# SD_-_Sensor_2021-02-24.net
KiCad netlist of a schematic drawn in EasyEDA
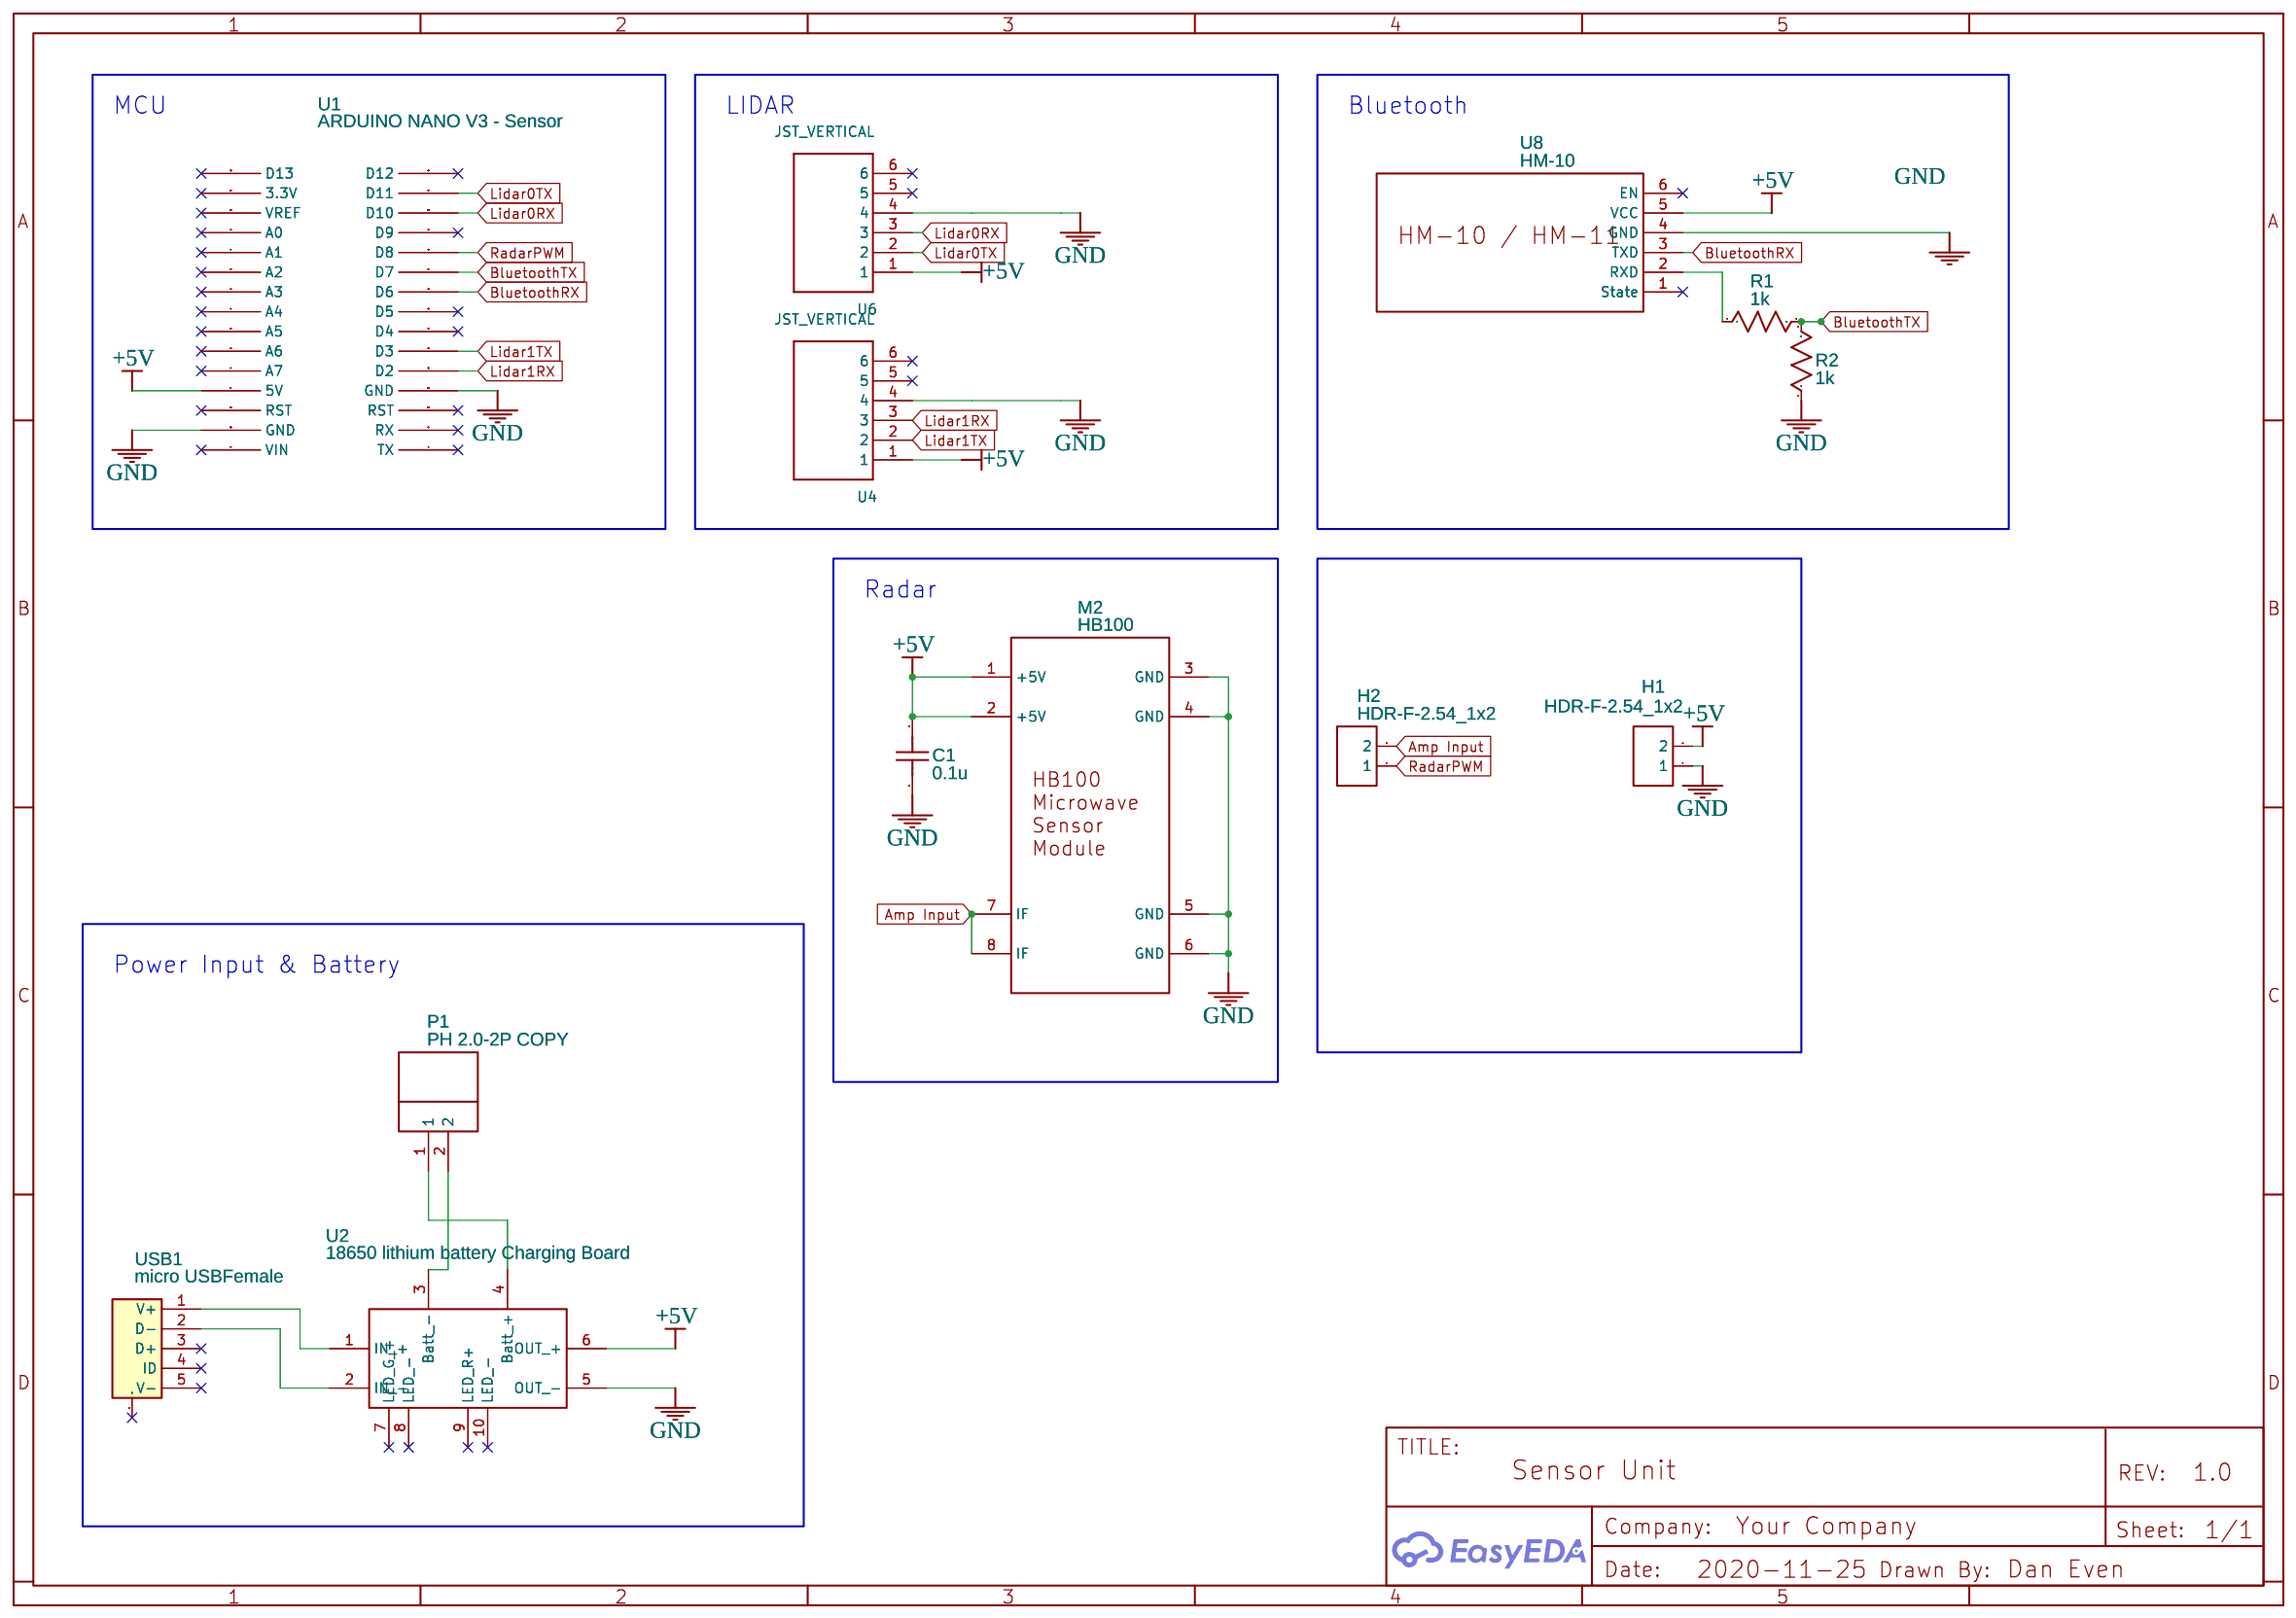
[diagram p0: schematic sheet]

(export (version "E")
  (design (tool "Eeschema 10.0.6"))
  (components
    (comp (ref "C1") (value "0.1u") (libsource (lib "") (part "C_RAD-0.1_US")))
    (comp (ref "H1")
      (value "HDR-F-2.54_1x2")
      (fields (field (name "BOM_Supplier Part") "C49661"))
      (libsource (lib "") (part "HDR-F-2.54_1x2"))
    )
    (comp (ref "H2")
      (value "HDR-F-2.54_1x2")
      (fields (field (name "BOM_Supplier Part") "C49661"))
      (libsource (lib "") (part "HDR-F-2.54_1x2"))
    )
    (comp (ref "M2") (value "HB100") (libsource (lib "") (part "HB100")))
    (comp (ref "P1")
      (value "PH 2.0-2P COPY")
      (fields (field (name "BOM_Manufacturer Part") "PH 2.0-2P"))
      (libsource (lib "") (part "PH 2.0-2P COPY"))
    )
    (comp (ref "R1") (value "1k") (libsource (lib "") (part "R_AXIAL-0.4_US_1")))
    (comp (ref "R2") (value "1k") (libsource (lib "") (part "R_AXIAL-0.4_US")))
    (comp (ref "U1")
      (value "ARDUINO NANO V3 - Sensor")
      (fields (field (name "BOM_Manufacturer Part") "arduino_nano1"))
      (libsource (lib "") (part "ARDUINO NANO V3"))
    )
    (comp (ref "U2")
      (value "18650 lithium battery Charging Board")
      (libsource (lib "") (part "18650 lithium battery Charging Board"))
    )
    (comp (ref "U4") (value "JST_VERTICAL") (libsource (lib "") (part "Unknown_405_-600")))
    (comp (ref "U6") (value "JST_VERTICAL") (libsource (lib "") (part "Unknown_405_-695")))
    (comp (ref "U8") (value "HM-10") (libsource (lib "") (part "HM-10")))
    (comp (ref "USB1")
      (value "micro USBFemale")
      (fields (field (name "BOM_Supplier Part") "C10418"))
      (libsource (lib "") (part "micro USBFemale"))
    )
  )
  (nets
    (net (code "1") (name "+5V") (class "Default")
      (node (ref "C1") (pin "2") (pinfunction "2_2") (pintype "unspecified"))
      (node (ref "H1") (pin "2") (pinfunction "2_2") (pintype "input"))
      (node (ref "M2") (pin "1") (pinfunction "+5V_1") (pintype "unspecified"))
      (node (ref "M2") (pin "2") (pinfunction "+5V_2") (pintype "unspecified"))
      (node (ref "U1") (pin "5V") (pinfunction "5V_5V") (pintype "unspecified"))
      (node (ref "U2") (pin "6") (pinfunction "OUT_+_6") (pintype "unspecified"))
      (node (ref "U4") (pin "1") (pinfunction "1_1") (pintype "bidirectional"))
      (node (ref "U6") (pin "1") (pinfunction "1_1") (pintype "bidirectional"))
      (node (ref "U8") (pin "5") (pinfunction "VCC_5") (pintype "unspecified"))
    )
    (net (code "2") (name "Amp Input") (class "Default")
      (node (ref "H2") (pin "2") (pinfunction "2_2") (pintype "input"))
      (node (ref "M2") (pin "7") (pinfunction "IF_7") (pintype "unspecified"))
      (node (ref "M2") (pin "8") (pinfunction "IF_8") (pintype "unspecified"))
    )
    (net (code "3") (name "BluetoothRX") (class "Default")
      (node (ref "U1") (pin "D6") (pinfunction "D6_D6") (pintype "unspecified"))
      (node (ref "U8") (pin "3") (pinfunction "TXD_3") (pintype "unspecified"))
    )
    (net (code "4") (name "BluetoothTX") (class "Default")
      (node (ref "R1") (pin "2") (pinfunction "2_2") (pintype "unspecified"))
      (node (ref "R2") (pin "2") (pinfunction "2_2") (pintype "unspecified"))
      (node (ref "U1") (pin "D7") (pinfunction "D7_D7") (pintype "unspecified"))
    )
    (net (code "5") (name "GND") (class "Default")
      (node (ref "C1") (pin "1") (pinfunction "1_1") (pintype "unspecified"))
      (node (ref "H1") (pin "1") (pinfunction "1_1") (pintype "input"))
      (node (ref "M2") (pin "3") (pinfunction "GND_3") (pintype "unspecified"))
      (node (ref "M2") (pin "4") (pinfunction "GND_4") (pintype "unspecified"))
      (node (ref "M2") (pin "5") (pinfunction "GND_5") (pintype "unspecified"))
      (node (ref "M2") (pin "6") (pinfunction "GND_6") (pintype "unspecified"))
      (node (ref "R2") (pin "1") (pinfunction "1_1") (pintype "unspecified"))
      (node (ref "U1") (pin "GND1") (pinfunction "GND_GND1") (pintype "unspecified"))
      (node (ref "U1") (pin "GND2") (pinfunction "GND_GND2") (pintype "unspecified"))
      (node (ref "U2") (pin "5") (pinfunction "OUT_-_5") (pintype "unspecified"))
      (node (ref "U4") (pin "4") (pinfunction "4_4") (pintype "bidirectional"))
      (node (ref "U6") (pin "4") (pinfunction "4_4") (pintype "bidirectional"))
      (node (ref "U8") (pin "4") (pinfunction "GND_4") (pintype "unspecified"))
    )
    (net (code "6") (name "Lidar0RX") (class "Default")
      (node (ref "U1") (pin "D10") (pinfunction "D10_D10") (pintype "unspecified"))
      (node (ref "U6") (pin "3") (pinfunction "3_3") (pintype "bidirectional"))
    )
    (net (code "7") (name "Lidar0TX") (class "Default")
      (node (ref "U1") (pin "D11") (pinfunction "D11_D11") (pintype "unspecified"))
      (node (ref "U6") (pin "2") (pinfunction "2_2") (pintype "bidirectional"))
    )
    (net (code "8") (name "Lidar1RX") (class "Default")
      (node (ref "U1") (pin "D2") (pinfunction "D2_D2") (pintype "unspecified"))
      (node (ref "U4") (pin "3") (pinfunction "3_3") (pintype "bidirectional"))
    )
    (net (code "9") (name "Lidar1TX") (class "Default")
      (node (ref "U1") (pin "D3") (pinfunction "D3_D3") (pintype "unspecified"))
      (node (ref "U4") (pin "2") (pinfunction "2_2") (pintype "bidirectional"))
    )
    (net (code "10") (name "Net-(U2-Batt_+)") (class "Default")
      (node (ref "P1") (pin "1") (pinfunction "1_1") (pintype "unspecified"))
      (node (ref "U2") (pin "4") (pinfunction "Batt_+_4") (pintype "unspecified"))
    )
    (net (code "11") (name "Net-(U2-Batt_-)") (class "Default")
      (node (ref "P1") (pin "2") (pinfunction "2_2") (pintype "unspecified"))
      (node (ref "U2") (pin "3") (pinfunction "Batt_-_3") (pintype "unspecified"))
    )
    (net (code "12") (name "Net-(U2-IN_+)") (class "Default")
      (node (ref "U2") (pin "1") (pinfunction "IN_+_1") (pintype "unspecified"))
      (node (ref "USB1") (pin "1") (pinfunction "V+_1") (pintype "unspecified"))
    )
    (net (code "13") (name "Net-(U2-IN_-)") (class "Default")
      (node (ref "U2") (pin "2") (pinfunction "IN_-_2") (pintype "unspecified"))
      (node (ref "USB1") (pin "2") (pinfunction "D-_2") (pintype "unspecified"))
    )
    (net (code "14") (name "Net-(U8-RXD)") (class "Default")
      (node (ref "R1") (pin "1") (pinfunction "1_1") (pintype "unspecified"))
      (node (ref "U8") (pin "2") (pinfunction "RXD_2") (pintype "unspecified"))
    )
    (net (code "15") (name "RadarPWM") (class "Default")
      (node (ref "H2") (pin "1") (pinfunction "1_1") (pintype "input"))
      (node (ref "U1") (pin "D8") (pinfunction "D8_D8") (pintype "unspecified"))
    )
    (net (code "16") (name "unconnected-(U1-Pad3.3V)") (class "Default")
      (node (ref "U1") (pin "3.3V") (pinfunction "3.3V_3.3V") (pintype "unspecified+no_connect"))
    )
    (net (code "17") (name "unconnected-(U1-PadA0)") (class "Default")
      (node (ref "U1") (pin "A0") (pinfunction "A0_A0") (pintype "unspecified+no_connect"))
    )
    (net (code "18") (name "unconnected-(U1-PadA1)") (class "Default")
      (node (ref "U1") (pin "A1") (pinfunction "A1_A1") (pintype "unspecified+no_connect"))
    )
    (net (code "19") (name "unconnected-(U1-PadA2)") (class "Default")
      (node (ref "U1") (pin "A2") (pinfunction "A2_A2") (pintype "unspecified+no_connect"))
    )
    (net (code "20") (name "unconnected-(U1-PadA3)") (class "Default")
      (node (ref "U1") (pin "A3") (pinfunction "A3_A3") (pintype "unspecified+no_connect"))
    )
    (net (code "21") (name "unconnected-(U1-PadA4)") (class "Default")
      (node (ref "U1") (pin "A4") (pinfunction "A4_A4") (pintype "unspecified+no_connect"))
    )
    (net (code "22") (name "unconnected-(U1-PadA5)") (class "Default")
      (node (ref "U1") (pin "A5") (pinfunction "A5_A5") (pintype "unspecified+no_connect"))
    )
    (net (code "23") (name "unconnected-(U1-PadA6)") (class "Default")
      (node (ref "U1") (pin "A6") (pinfunction "A6_A6") (pintype "unspecified+no_connect"))
    )
    (net (code "24") (name "unconnected-(U1-PadA7)") (class "Default")
      (node (ref "U1") (pin "A7") (pinfunction "A7_A7") (pintype "unspecified+no_connect"))
    )
    (net (code "25") (name "unconnected-(U1-PadD4)") (class "Default")
      (node (ref "U1") (pin "D4") (pinfunction "D4_D4") (pintype "unspecified+no_connect"))
    )
    (net (code "26") (name "unconnected-(U1-PadD5)") (class "Default")
      (node (ref "U1") (pin "D5") (pinfunction "D5_D5") (pintype "unspecified+no_connect"))
    )
    (net (code "27") (name "unconnected-(U1-PadD9)") (class "Default")
      (node (ref "U1") (pin "D9") (pinfunction "D9_D9") (pintype "unspecified+no_connect"))
    )
    (net (code "28") (name "unconnected-(U1-PadD12)") (class "Default")
      (node (ref "U1") (pin "D12") (pinfunction "D12_D12") (pintype "unspecified+no_connect"))
    )
    (net (code "29") (name "unconnected-(U1-PadD13)") (class "Default")
      (node (ref "U1") (pin "D13") (pinfunction "D13_D13") (pintype "unspecified+no_connect"))
    )
    (net (code "30") (name "unconnected-(U1-PadRX)") (class "Default")
      (node (ref "U1") (pin "RX") (pinfunction "RX_RX") (pintype "unspecified+no_connect"))
    )
    (net (code "31") (name "unconnected-(U1-PadTX)") (class "Default")
      (node (ref "U1") (pin "TX") (pinfunction "TX_TX") (pintype "unspecified+no_connect"))
    )
    (net (code "32") (name "unconnected-(U1-PadVIN)") (class "Default")
      (node (ref "U1") (pin "VIN") (pinfunction "VIN_VIN") (pintype "unspecified+no_connect"))
    )
    (net (code "33") (name "unconnected-(U1-PadVREF)") (class "Default")
      (node (ref "U1") (pin "VREF") (pinfunction "VREF_VREF") (pintype "unspecified+no_connect"))
    )
    (net (code "34") (name "unconnected-(U1-RST-PadRST1)") (class "Default")
      (node (ref "U1") (pin "RST1") (pinfunction "RST_RST1") (pintype "unspecified+no_connect"))
    )
    (net (code "35") (name "unconnected-(U1-RST-PadRST2)") (class "Default")
      (node (ref "U1") (pin "RST2") (pinfunction "RST_RST2") (pintype "unspecified+no_connect"))
    )
    (net (code "36") (name "unconnected-(U2-LED_--Pad8)") (class "Default")
      (node (ref "U2") (pin "8") (pinfunction "LED_-_8") (pintype "unspecified+no_connect"))
    )
    (net (code "37") (name "unconnected-(U2-LED_--Pad10)") (class "Default")
      (node (ref "U2") (pin "10") (pinfunction "LED_-_10") (pintype "unspecified+no_connect"))
    )
    (net (code "38") (name "unconnected-(U2-LED_G_+-Pad7)") (class "Default")
      (node (ref "U2") (pin "7") (pinfunction "LED_G_+_7") (pintype "unspecified+no_connect"))
    )
    (net (code "39") (name "unconnected-(U2-LED_R+-Pad9)") (class "Default")
      (node (ref "U2") (pin "9") (pinfunction "LED_R+_9") (pintype "unspecified+no_connect"))
    )
    (net (code "40") (name "unconnected-(U4-Pad5)") (class "Default")
      (node (ref "U4") (pin "5") (pinfunction "5_5") (pintype "bidirectional+no_connect"))
    )
    (net (code "41") (name "unconnected-(U4-Pad6)") (class "Default")
      (node (ref "U4") (pin "6") (pinfunction "6_6") (pintype "bidirectional+no_connect"))
    )
    (net (code "42") (name "unconnected-(U6-Pad5)") (class "Default")
      (node (ref "U6") (pin "5") (pinfunction "5_5") (pintype "bidirectional+no_connect"))
    )
    (net (code "43") (name "unconnected-(U6-Pad6)") (class "Default")
      (node (ref "U6") (pin "6") (pinfunction "6_6") (pintype "bidirectional+no_connect"))
    )
    (net (code "44") (name "unconnected-(U8-EN-Pad6)") (class "Default")
      (node (ref "U8") (pin "6") (pinfunction "EN_6") (pintype "unspecified+no_connect"))
    )
    (net (code "45") (name "unconnected-(U8-State-Pad1)") (class "Default")
      (node (ref "U8") (pin "1") (pinfunction "State_1") (pintype "unspecified+no_connect"))
    )
    (net (code "46") (name "unconnected-(USB1-D+-Pad3)") (class "Default")
      (node (ref "USB1") (pin "3") (pinfunction "D+_3") (pintype "unspecified+no_connect"))
    )
    (net (code "47") (name "unconnected-(USB1-ID-Pad4)") (class "Default")
      (node (ref "USB1") (pin "4") (pinfunction "ID_4") (pintype "unspecified+no_connect"))
    )
    (net (code "48") (name "unconnected-(USB1-MTN-Pad0)") (class "Default")
      (node (ref "USB1") (pin "0") (pinfunction "MTN_0") (pintype "input+no_connect"))
    )
    (net (code "49") (name "unconnected-(USB1-V--Pad5)") (class "Default")
      (node (ref "USB1") (pin "5") (pinfunction "V-_5") (pintype "unspecified+no_connect"))
    )
  )
)
